# Main.net
KiCad netlist of a schematic drawn in Altium Designer
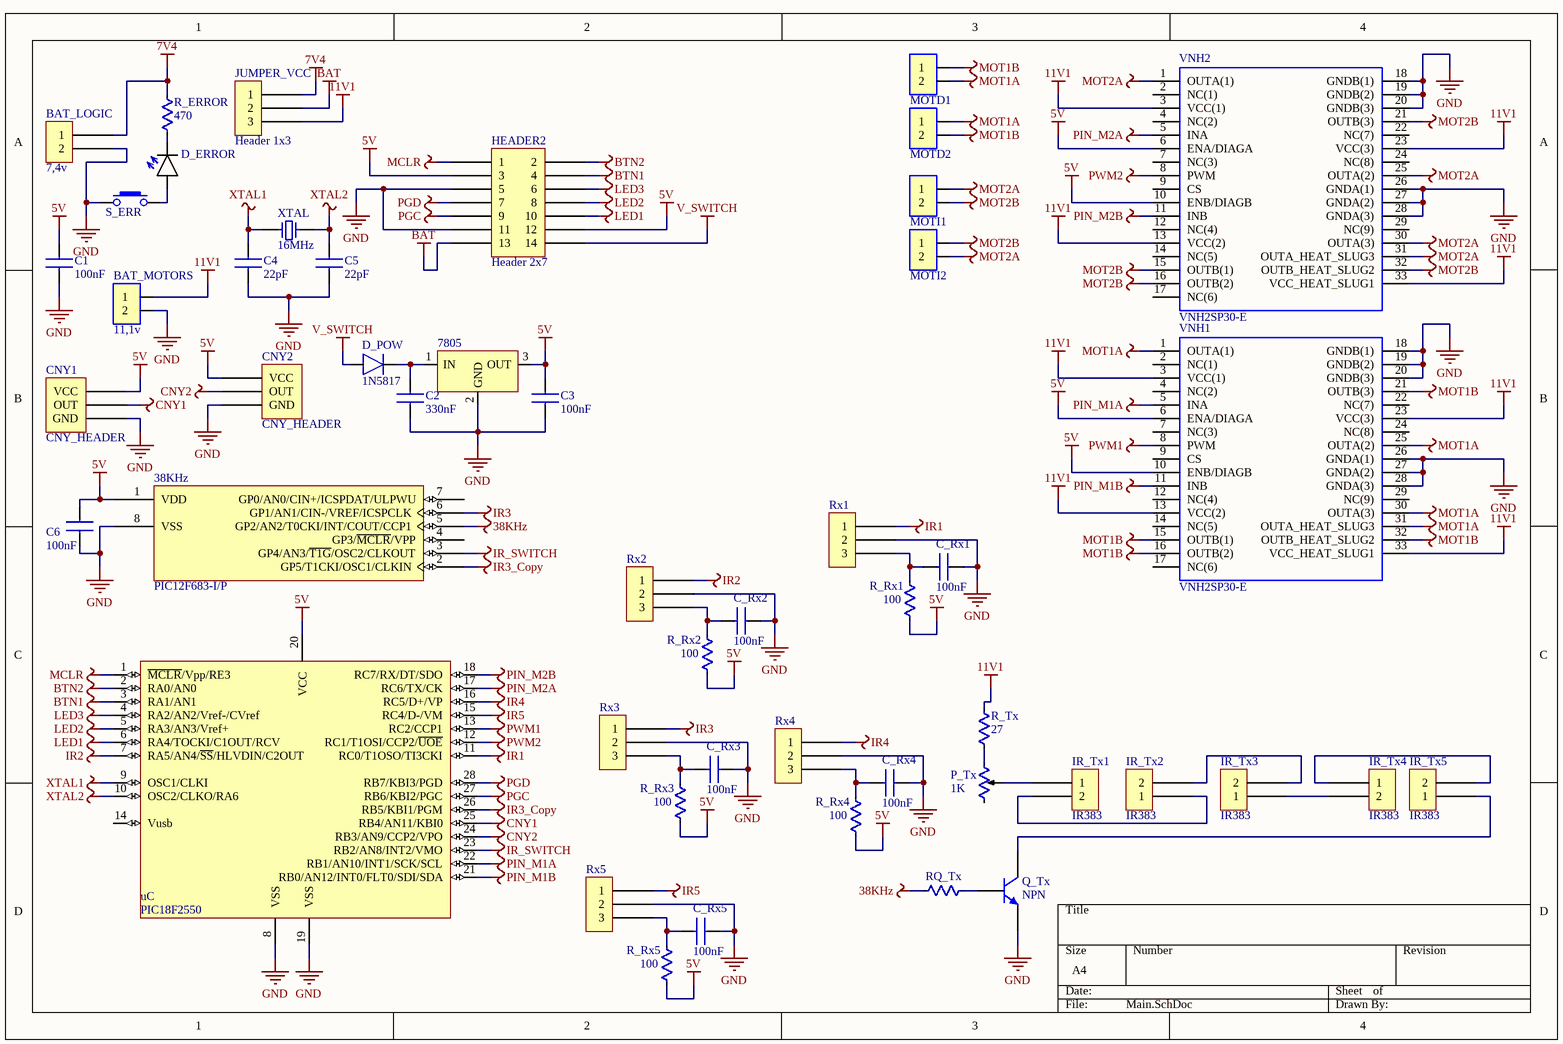
[diagram p0: Main.SchDoc]

(export (version "E")
  (design (tool "Eeschema 10.0.6"))
  (components
    (comp (ref "38KHz")
      (value "PIC12F683-I/P")
      (footprint "PDIP300-P8")
      (fields (field (name "PUBLISHER") "Altium Limited"))
      (libsource (lib "Microchip Microcontroller 8-Bit PIC12") (part "PIC12F683-I/P"))
    )
    (comp (ref "7805")
      (value "LM78XX")
      (footprint "TO-220-STRAIGHT")
      (libsource (lib "AltiumLibrary") (part "LM78XX"))
    )
    (comp (ref "BAT_LOGIC")
      (value "7,4v")
      (footprint "HEADER 1x2")
      (libsource (lib "") (part "Header 1x2_1"))
    )
    (comp (ref "BAT_MOTORS")
      (value "11,1v")
      (footprint "BLOCK_TERMINAL-2")
      (libsource (lib "AltiumLibrary") (part "2-BLOCK_TERMINAL"))
    )
    (comp (ref "C1")
      (value "100nF")
      (footprint "CAP-CER")
      (fields (field (name "Comment") "CAP-CER"))
      (libsource (lib "AltiumLibrary") (part "CAP-CER"))
    )
    (comp (ref "C2")
      (value "330nF")
      (footprint "CAP-CER")
      (fields (field (name "Comment") "CAP-CER"))
      (libsource (lib "AltiumLibrary") (part "CAP-CER"))
    )
    (comp (ref "C3")
      (value "100nF")
      (footprint "CAP-CER")
      (fields (field (name "Comment") "CAP-CER"))
      (libsource (lib "AltiumLibrary") (part "CAP-CER"))
    )
    (comp (ref "C4")
      (value "22pF")
      (footprint "CAP-CER")
      (fields (field (name "Comment") "CAP-CER"))
      (libsource (lib "AltiumLibrary") (part "CAP-CER"))
    )
    (comp (ref "C5")
      (value "22pF")
      (footprint "CAP-CER")
      (fields (field (name "Comment") "CAP-CER"))
      (libsource (lib "AltiumLibrary") (part "CAP-CER"))
    )
    (comp (ref "C6")
      (value "100nF")
      (footprint "CAP-CER")
      (fields (field (name "Comment") "CAP-CER"))
      (libsource (lib "AltiumLibrary") (part "CAP-CER"))
    )
    (comp (ref "CNY1")
      (value "CNY_HEADER")
      (footprint "CNY_HEADER")
      (libsource (lib "") (part "CNY_HEADER_1"))
    )
    (comp (ref "CNY2")
      (value "CNY_HEADER")
      (footprint "CNY_HEADER")
      (libsource (lib "AltiumLibrary") (part "CNY_HEADER"))
    )
    (comp (ref "C_Rx1")
      (value "100nF")
      (footprint "CAP-CER")
      (fields (field (name "Comment") "CAP-CER"))
      (libsource (lib "AltiumLibrary") (part "CAP-CER"))
    )
    (comp (ref "C_Rx2")
      (value "100nF")
      (footprint "CAP-CER")
      (fields (field (name "Comment") "CAP-CER"))
      (libsource (lib "AltiumLibrary") (part "CAP-CER"))
    )
    (comp (ref "C_Rx3")
      (value "100nF")
      (footprint "CAP-CER")
      (fields (field (name "Comment") "CAP-CER"))
      (libsource (lib "AltiumLibrary") (part "CAP-CER"))
    )
    (comp (ref "C_Rx4")
      (value "100nF")
      (footprint "CAP-CER")
      (fields (field (name "Comment") "CAP-CER"))
      (libsource (lib "AltiumLibrary") (part "CAP-CER"))
    )
    (comp (ref "C_Rx5")
      (value "100nF")
      (footprint "CAP-CER")
      (fields (field (name "Comment") "CAP-CER"))
      (libsource (lib "AltiumLibrary") (part "CAP-CER"))
    )
    (comp (ref "D_ERROR")
      (value "LED")
      (footprint "LED-3MM-RED")
      (libsource (lib "AltiumLibrary") (part "LED"))
    )
    (comp (ref "D_POW")
      (value "DIODE")
      (footprint "DO-41")
      (fields (field (name "NAME") "1N5817"))
      (libsource (lib "AltiumLibrary") (part "DIODE"))
    )
    (comp (ref "HEADER2")
      (value "Header 2x7")
      (footprint "HEADER 2x7")
      (libsource (lib "AltiumLibrary") (part "Header 2x7"))
    )
    (comp (ref "IR_Tx1")
      (value "IR383")
      (footprint "HEADER 1x2")
      (libsource (lib "AltiumLibrary") (part "Header 1x2"))
    )
    (comp (ref "IR_Tx2") (value "IR383") (footprint "HEADER 1x2") (libsource (lib "") (part "Header 1x2_2")))
    (comp (ref "IR_Tx3") (value "IR383") (footprint "HEADER 1x2") (libsource (lib "") (part "Header 1x2_2")))
    (comp (ref "IR_Tx4")
      (value "IR383")
      (footprint "HEADER 1x2")
      (libsource (lib "AltiumLibrary") (part "Header 1x2"))
    )
    (comp (ref "IR_Tx5") (value "IR383") (footprint "HEADER 1x2") (libsource (lib "") (part "Header 1x2_2")))
    (comp (ref "JUMPER_VCC")
      (value "Header 1x3")
      (footprint "Header 1x3")
      (libsource (lib "AltiumLibrary") (part "Header 1x3"))
    )
    (comp (ref "MOTD1")
      (value "2-BLOCK_TERMINAL")
      (footprint "BLOCK_TERMINAL-2")
      (libsource (lib "AltiumLibrary") (part "2-BLOCK_TERMINAL"))
    )
    (comp (ref "MOTD2")
      (value "2-BLOCK_TERMINAL")
      (footprint "BLOCK_TERMINAL-2")
      (libsource (lib "AltiumLibrary") (part "2-BLOCK_TERMINAL"))
    )
    (comp (ref "MOTI1")
      (value "2-BLOCK_TERMINAL")
      (footprint "BLOCK_TERMINAL-2")
      (libsource (lib "AltiumLibrary") (part "2-BLOCK_TERMINAL"))
    )
    (comp (ref "MOTI2")
      (value "2-BLOCK_TERMINAL")
      (footprint "BLOCK_TERMINAL-2")
      (libsource (lib "AltiumLibrary") (part "2-BLOCK_TERMINAL"))
    )
    (comp (ref "P_Tx")
      (value "1K")
      (footprint "POT-10TURN")
      (fields (field (name "Comment") "POT"))
      (libsource (lib "AltiumLibrary") (part "POT"))
    )
    (comp (ref "Q_Tx") (value "NPN") (footprint "TO-92") (libsource (lib "AltiumLibrary") (part "NPN")))
    (comp (ref "RQ_Tx") (value "RES") (footprint "RES-Axial-400mil") (libsource (lib "") (part "RES_1")))
    (comp (ref "Rx1")
      (value "Header 1x3")
      (footprint "Header 1x3")
      (libsource (lib "AltiumLibrary") (part "Header 1x3"))
    )
    (comp (ref "Rx2")
      (value "Header 1x3")
      (footprint "Header 1x3")
      (libsource (lib "AltiumLibrary") (part "Header 1x3"))
    )
    (comp (ref "Rx3")
      (value "Header 1x3")
      (footprint "Header 1x3")
      (libsource (lib "AltiumLibrary") (part "Header 1x3"))
    )
    (comp (ref "Rx4")
      (value "Header 1x3")
      (footprint "Header 1x3")
      (libsource (lib "AltiumLibrary") (part "Header 1x3"))
    )
    (comp (ref "Rx5")
      (value "Header 1x3")
      (footprint "Header 1x3")
      (libsource (lib "AltiumLibrary") (part "Header 1x3"))
    )
    (comp (ref "R_ERROR")
      (value "470")
      (footprint "RES-Axial-400mil")
      (fields (field (name "Comment") "RES"))
      (libsource (lib "AltiumLibrary") (part "RES"))
    )
    (comp (ref "R_Rx1")
      (value "100")
      (footprint "RES-Axial-400mil")
      (fields (field (name "Comment") "RES"))
      (libsource (lib "AltiumLibrary") (part "RES"))
    )
    (comp (ref "R_Rx2")
      (value "100")
      (footprint "RES-Axial-400mil")
      (fields (field (name "Comment") "RES"))
      (libsource (lib "AltiumLibrary") (part "RES"))
    )
    (comp (ref "R_Rx3")
      (value "100")
      (footprint "RES-Axial-400mil")
      (fields (field (name "Comment") "RES"))
      (libsource (lib "AltiumLibrary") (part "RES"))
    )
    (comp (ref "R_Rx4")
      (value "100")
      (footprint "RES-Axial-400mil")
      (fields (field (name "Comment") "RES"))
      (libsource (lib "AltiumLibrary") (part "RES"))
    )
    (comp (ref "R_Rx5")
      (value "100")
      (footprint "RES-Axial-400mil")
      (fields (field (name "Comment") "RES"))
      (libsource (lib "AltiumLibrary") (part "RES"))
    )
    (comp (ref "R_Tx")
      (value "27")
      (footprint "RES-Axial-400mil")
      (fields (field (name "Comment") "RES"))
      (libsource (lib "AltiumLibrary") (part "RES"))
    )
    (comp (ref "S_ERR")
      (value "BUTTON_SMALL_4PIN")
      (footprint "TACT_SWITCH-SMALL-4PIN")
      (libsource (lib "AltiumLibrary") (part "BUTTON_SMALL_4PIN"))
    )
    (comp (ref "uC")
      (value "PIC18F2550")
      (footprint "DIP28")
      (libsource (lib "AltiumLibrary") (part "PIC18F2550"))
    )
    (comp (ref "VNH1")
      (value "VNH2SP30-E")
      (footprint "MULTIPOWER-SO-30")
      (fields (field (name "DIGIKEY PART NUMBER") "497-4500-5-ND"))
      (libsource (lib "AltiumLibrary") (part "VNH2SP30-E"))
    )
    (comp (ref "VNH2")
      (value "VNH2SP30-E")
      (footprint "MULTIPOWER-SO-30")
      (fields (field (name "DIGIKEY PART NUMBER") "497-4500-5-ND"))
      (libsource (lib "AltiumLibrary") (part "VNH2SP30-E"))
    )
    (comp (ref "XTAL")
      (value "XTAL")
      (footprint "HC-49/S")
      (fields (field (name "FREQUENCY") "16MHz"))
      (libsource (lib "AltiumLibrary") (part "XTAL"))
    )
  )
  (nets
    (net (code "1") (name "5V") (class "Default")
      (node (ref "38KHz") (pin "1") (pinfunction "VDD_1") (pintype "power_in"))
      (node (ref "7805") (pin "3") (pinfunction "OUT_3") (pintype "power_in"))
      (node (ref "C1") (pin "2") (pintype "passive"))
      (node (ref "C3") (pin "2") (pintype "passive"))
      (node (ref "C6") (pin "2") (pintype "passive"))
      (node (ref "CNY1") (pin "2") (pinfunction "VCC_2") (pintype "passive"))
      (node (ref "CNY2") (pin "2") (pinfunction "VCC_2") (pintype "passive"))
      (node (ref "HEADER2") (pin "12") (pinfunction "12_12") (pintype "passive"))
      (node (ref "HEADER2") (pin "3") (pinfunction "3_3") (pintype "passive"))
      (node (ref "R_Rx1") (pin "1") (pintype "passive"))
      (node (ref "R_Rx2") (pin "1") (pintype "passive"))
      (node (ref "R_Rx3") (pin "1") (pintype "passive"))
      (node (ref "R_Rx4") (pin "1") (pintype "passive"))
      (node (ref "R_Rx5") (pin "1") (pintype "passive"))
      (node (ref "VNH1") (pin "10") (pinfunction "ENB/DIAGB_10") (pintype "passive"))
      (node (ref "VNH1") (pin "6") (pinfunction "ENA/DIAGA_6") (pintype "passive"))
      (node (ref "VNH2") (pin "10") (pinfunction "ENB/DIAGB_10") (pintype "passive"))
      (node (ref "VNH2") (pin "6") (pinfunction "ENA/DIAGA_6") (pintype "passive"))
      (node (ref "uC") (pin "20") (pinfunction "VCC_20") (pintype "power_in"))
    )
    (net (code "2") (name "7V4") (class "Default")
      (node (ref "BAT_LOGIC") (pin "1") (pinfunction "1_1") (pintype "passive"))
      (node (ref "JUMPER_VCC") (pin "1") (pinfunction "1_1") (pintype "passive"))
      (node (ref "R_ERROR") (pin "2") (pintype "passive"))
    )
    (net (code "3") (name "11V1") (class "Default")
      (node (ref "BAT_MOTORS") (pin "1") (pinfunction "1_1") (pintype "passive"))
      (node (ref "JUMPER_VCC") (pin "3") (pinfunction "3_3") (pintype "passive"))
      (node (ref "R_Tx") (pin "2") (pintype "passive"))
      (node (ref "VNH1") (pin "13") (pinfunction "VCC(2)_13") (pintype "passive"))
      (node (ref "VNH1") (pin "23") (pinfunction "VCC(3)_23") (pintype "passive"))
      (node (ref "VNH1") (pin "3") (pinfunction "VCC(1)_3") (pintype "passive"))
      (node (ref "VNH1") (pin "33") (pinfunction "VCC_HEAT_SLUG1_33") (pintype "passive"))
      (node (ref "VNH2") (pin "13") (pinfunction "VCC(2)_13") (pintype "passive"))
      (node (ref "VNH2") (pin "23") (pinfunction "VCC(3)_23") (pintype "passive"))
      (node (ref "VNH2") (pin "3") (pinfunction "VCC(1)_3") (pintype "passive"))
      (node (ref "VNH2") (pin "33") (pinfunction "VCC_HEAT_SLUG1_33") (pintype "passive"))
    )
    (net (code "4") (name "38KHz") (class "Default")
      (node (ref "38KHz") (pin "5") (pinfunction "GP2/AN2/T0CKI/INT/COUT/CCP1_5") (pintype "bidirectional"))
      (node (ref "RQ_Tx") (pin "1") (pintype "passive"))
    )
    (net (code "5") (name "BAT") (class "Default")
      (node (ref "HEADER2") (pin "13") (pinfunction "13_13") (pintype "passive"))
      (node (ref "JUMPER_VCC") (pin "2") (pinfunction "2_2") (pintype "passive"))
    )
    (net (code "6") (name "BTN1") (class "Default")
      (node (ref "HEADER2") (pin "4") (pinfunction "4_4") (pintype "passive"))
      (node (ref "uC") (pin "3") (pinfunction "RA1/AN1_3") (pintype "bidirectional"))
    )
    (net (code "7") (name "BTN2") (class "Default")
      (node (ref "HEADER2") (pin "2") (pinfunction "2_2") (pintype "passive"))
      (node (ref "uC") (pin "2") (pinfunction "RA0/AN0_2") (pintype "bidirectional"))
    )
    (net (code "8") (name "CNY1") (class "Default")
      (node (ref "CNY1") (pin "3") (pinfunction "OUT_3") (pintype "passive"))
      (node (ref "uC") (pin "25") (pinfunction "RB4/AN11/KBI0_25") (pintype "bidirectional"))
    )
    (net (code "9") (name "CNY2") (class "Default")
      (node (ref "CNY2") (pin "3") (pinfunction "OUT_3") (pintype "passive"))
      (node (ref "uC") (pin "24") (pinfunction "RB3/AN9/CCP2/VPO_24") (pintype "bidirectional"))
    )
    (net (code "10") (name "GND") (class "Default")
      (node (ref "38KHz") (pin "8") (pinfunction "VSS_8") (pintype "power_in"))
      (node (ref "7805") (pin "2") (pinfunction "GND_2") (pintype "power_in"))
      (node (ref "BAT_LOGIC") (pin "2") (pinfunction "2_2") (pintype "passive"))
      (node (ref "BAT_MOTORS") (pin "2") (pinfunction "2_2") (pintype "passive"))
      (node (ref "C1") (pin "1") (pintype "passive"))
      (node (ref "C2") (pin "1") (pintype "passive"))
      (node (ref "C3") (pin "1") (pintype "passive"))
      (node (ref "C4") (pin "1") (pintype "passive"))
      (node (ref "C5") (pin "1") (pintype "passive"))
      (node (ref "C6") (pin "1") (pintype "passive"))
      (node (ref "CNY1") (pin "1") (pinfunction "GND_1") (pintype "passive"))
      (node (ref "CNY2") (pin "1") (pinfunction "GND_1") (pintype "passive"))
      (node (ref "C_Rx1") (pin "2") (pintype "passive"))
      (node (ref "C_Rx2") (pin "2") (pintype "passive"))
      (node (ref "C_Rx3") (pin "2") (pintype "passive"))
      (node (ref "C_Rx4") (pin "2") (pintype "passive"))
      (node (ref "C_Rx5") (pin "2") (pintype "passive"))
      (node (ref "HEADER2") (pin "11") (pinfunction "11_11") (pintype "passive"))
      (node (ref "HEADER2") (pin "5") (pinfunction "5_5") (pintype "passive"))
      (node (ref "Q_Tx") (pin "E") (pinfunction "E_E") (pintype "passive"))
      (node (ref "Rx1") (pin "2") (pinfunction "2_2") (pintype "passive"))
      (node (ref "Rx2") (pin "2") (pinfunction "2_2") (pintype "passive"))
      (node (ref "Rx3") (pin "2") (pinfunction "2_2") (pintype "passive"))
      (node (ref "Rx4") (pin "2") (pinfunction "2_2") (pintype "passive"))
      (node (ref "Rx5") (pin "2") (pinfunction "2_2") (pintype "passive"))
      (node (ref "S_ERR") (pin "1") (pintype "passive"))
      (node (ref "VNH1") (pin "18") (pinfunction "GNDB(1)_18") (pintype "passive"))
      (node (ref "VNH1") (pin "19") (pinfunction "GNDB(2)_19") (pintype "passive"))
      (node (ref "VNH1") (pin "20") (pinfunction "GNDB(3)_20") (pintype "passive"))
      (node (ref "VNH1") (pin "26") (pinfunction "GNDA(1)_26") (pintype "passive"))
      (node (ref "VNH1") (pin "27") (pinfunction "GNDA(2)_27") (pintype "passive"))
      (node (ref "VNH1") (pin "28") (pinfunction "GNDA(3)_28") (pintype "passive"))
      (node (ref "VNH2") (pin "18") (pinfunction "GNDB(1)_18") (pintype "passive"))
      (node (ref "VNH2") (pin "19") (pinfunction "GNDB(2)_19") (pintype "passive"))
      (node (ref "VNH2") (pin "20") (pinfunction "GNDB(3)_20") (pintype "passive"))
      (node (ref "VNH2") (pin "26") (pinfunction "GNDA(1)_26") (pintype "passive"))
      (node (ref "VNH2") (pin "27") (pinfunction "GNDA(2)_27") (pintype "passive"))
      (node (ref "VNH2") (pin "28") (pinfunction "GNDA(3)_28") (pintype "passive"))
      (node (ref "uC") (pin "19") (pinfunction "VSS_19") (pintype "power_in"))
      (node (ref "uC") (pin "8") (pinfunction "VSS_8") (pintype "power_in"))
    )
    (net (code "11") (name "IR1") (class "Default")
      (node (ref "Rx1") (pin "1") (pinfunction "1_1") (pintype "passive"))
      (node (ref "uC") (pin "11") (pinfunction "RC0/T1OSO/TI3CKI_11") (pintype "bidirectional"))
    )
    (net (code "12") (name "IR2") (class "Default")
      (node (ref "Rx2") (pin "1") (pinfunction "1_1") (pintype "passive"))
      (node (ref "uC") (pin "7") (pinfunction "RA5/AN4/~{SS}/HLVDIN/C2OUT_7") (pintype "bidirectional"))
    )
    (net (code "13") (name "IR3") (class "Default")
      (node (ref "38KHz") (pin "6") (pinfunction "GP1/AN1/CIN-/VREF/ICSPCLK_6") (pintype "bidirectional"))
      (node (ref "Rx3") (pin "1") (pinfunction "1_1") (pintype "passive"))
    )
    (net (code "14") (name "IR3_Copy") (class "Default")
      (node (ref "38KHz") (pin "2") (pinfunction "GP5/T1CKI/OSC1/CLKIN_2") (pintype "bidirectional"))
      (node (ref "uC") (pin "26") (pinfunction "RB5/KBI1/PGM_26") (pintype "bidirectional"))
    )
    (net (code "15") (name "IR4") (class "Default")
      (node (ref "Rx4") (pin "1") (pinfunction "1_1") (pintype "passive"))
      (node (ref "uC") (pin "16") (pinfunction "RC5/D+/VP_16") (pintype "bidirectional"))
    )
    (net (code "16") (name "IR5") (class "Default")
      (node (ref "Rx5") (pin "1") (pinfunction "1_1") (pintype "passive"))
      (node (ref "uC") (pin "15") (pinfunction "RC4/D-/VM_15") (pintype "bidirectional"))
    )
    (net (code "17") (name "IR_SWITCH") (class "Default")
      (node (ref "38KHz") (pin "3") (pinfunction "GP4/AN3/~{T1G}/OSC2/CLKOUT_3") (pintype "bidirectional"))
      (node (ref "uC") (pin "23") (pinfunction "RB2/AN8/INT2/VMO_23") (pintype "bidirectional"))
    )
    (net (code "18") (name "LED1") (class "Default")
      (node (ref "HEADER2") (pin "10") (pinfunction "10_10") (pintype "passive"))
      (node (ref "uC") (pin "6") (pinfunction "RA4/TOCKI/C1OUT/RCV_6") (pintype "bidirectional"))
    )
    (net (code "19") (name "LED2") (class "Default")
      (node (ref "HEADER2") (pin "8") (pinfunction "8_8") (pintype "passive"))
      (node (ref "uC") (pin "5") (pinfunction "RA3/AN3/Vref+_5") (pintype "bidirectional"))
    )
    (net (code "20") (name "LED3") (class "Default")
      (node (ref "HEADER2") (pin "6") (pinfunction "6_6") (pintype "passive"))
      (node (ref "uC") (pin "4") (pinfunction "RA2/AN2/Vref-/CVref_4") (pintype "bidirectional"))
    )
    (net (code "21") (name "MCLR") (class "Default")
      (node (ref "HEADER2") (pin "1") (pinfunction "1_1") (pintype "passive"))
      (node (ref "uC") (pin "1") (pinfunction "~{MCLR}/Vpp/RE3_1") (pintype "bidirectional"))
    )
    (net (code "22") (name "MOT1A") (class "Default")
      (node (ref "MOTD1") (pin "2") (pinfunction "2_2") (pintype "passive"))
      (node (ref "MOTD2") (pin "1") (pinfunction "1_1") (pintype "passive"))
      (node (ref "VNH1") (pin "1") (pinfunction "OUTA(1)_1") (pintype "passive"))
      (node (ref "VNH1") (pin "25") (pinfunction "OUTA(2)_25") (pintype "passive"))
      (node (ref "VNH1") (pin "30") (pinfunction "OUTA(3)_30") (pintype "passive"))
      (node (ref "VNH1") (pin "31") (pinfunction "OUTA_HEAT_SLUG3_31") (pintype "passive"))
    )
    (net (code "23") (name "MOT1B") (class "Default")
      (node (ref "MOTD1") (pin "1") (pinfunction "1_1") (pintype "passive"))
      (node (ref "MOTD2") (pin "2") (pinfunction "2_2") (pintype "passive"))
      (node (ref "VNH1") (pin "15") (pinfunction "OUTB(1)_15") (pintype "passive"))
      (node (ref "VNH1") (pin "16") (pinfunction "OUTB(2)_16") (pintype "passive"))
      (node (ref "VNH1") (pin "21") (pinfunction "OUTB(3)_21") (pintype "passive"))
      (node (ref "VNH1") (pin "32") (pinfunction "OUTB_HEAT_SLUG2_32") (pintype "passive"))
    )
    (net (code "24") (name "MOT2A") (class "Default")
      (node (ref "MOTI1") (pin "1") (pinfunction "1_1") (pintype "passive"))
      (node (ref "MOTI2") (pin "2") (pinfunction "2_2") (pintype "passive"))
      (node (ref "VNH2") (pin "1") (pinfunction "OUTA(1)_1") (pintype "passive"))
      (node (ref "VNH2") (pin "25") (pinfunction "OUTA(2)_25") (pintype "passive"))
      (node (ref "VNH2") (pin "30") (pinfunction "OUTA(3)_30") (pintype "passive"))
      (node (ref "VNH2") (pin "31") (pinfunction "OUTA_HEAT_SLUG3_31") (pintype "passive"))
    )
    (net (code "25") (name "MOT2B") (class "Default")
      (node (ref "MOTI1") (pin "2") (pinfunction "2_2") (pintype "passive"))
      (node (ref "MOTI2") (pin "1") (pinfunction "1_1") (pintype "passive"))
      (node (ref "VNH2") (pin "15") (pinfunction "OUTB(1)_15") (pintype "passive"))
      (node (ref "VNH2") (pin "16") (pinfunction "OUTB(2)_16") (pintype "passive"))
      (node (ref "VNH2") (pin "21") (pinfunction "OUTB(3)_21") (pintype "passive"))
      (node (ref "VNH2") (pin "32") (pinfunction "OUTB_HEAT_SLUG2_32") (pintype "passive"))
    )
    (net (code "26") (name "Net-(7805-IN)") (class "Default")
      (node (ref "7805") (pin "1") (pinfunction "IN_1") (pintype "power_in"))
      (node (ref "C2") (pin "2") (pintype "passive"))
      (node (ref "D_POW") (pin "K") (pintype "passive"))
    )
    (net (code "27") (name "Net-(C_Rx1-Pad1)") (class "Default")
      (node (ref "C_Rx1") (pin "1") (pintype "passive"))
      (node (ref "R_Rx1") (pin "2") (pintype "passive"))
      (node (ref "Rx1") (pin "3") (pinfunction "3_3") (pintype "passive"))
    )
    (net (code "28") (name "Net-(C_Rx2-Pad1)") (class "Default")
      (node (ref "C_Rx2") (pin "1") (pintype "passive"))
      (node (ref "R_Rx2") (pin "2") (pintype "passive"))
      (node (ref "Rx2") (pin "3") (pinfunction "3_3") (pintype "passive"))
    )
    (net (code "29") (name "Net-(C_Rx3-Pad1)") (class "Default")
      (node (ref "C_Rx3") (pin "1") (pintype "passive"))
      (node (ref "R_Rx3") (pin "2") (pintype "passive"))
      (node (ref "Rx3") (pin "3") (pinfunction "3_3") (pintype "passive"))
    )
    (net (code "30") (name "Net-(C_Rx4-Pad1)") (class "Default")
      (node (ref "C_Rx4") (pin "1") (pintype "passive"))
      (node (ref "R_Rx4") (pin "2") (pintype "passive"))
      (node (ref "Rx4") (pin "3") (pinfunction "3_3") (pintype "passive"))
    )
    (net (code "31") (name "Net-(C_Rx5-Pad1)") (class "Default")
      (node (ref "C_Rx5") (pin "1") (pintype "passive"))
      (node (ref "R_Rx5") (pin "2") (pintype "passive"))
      (node (ref "Rx5") (pin "3") (pinfunction "3_3") (pintype "passive"))
    )
    (net (code "32") (name "Net-(D_ERROR-PadA)") (class "Default")
      (node (ref "D_ERROR") (pin "A") (pintype "passive"))
      (node (ref "S_ERR") (pin "2") (pintype "passive"))
    )
    (net (code "33") (name "Net-(D_ERROR-PadK)") (class "Default")
      (node (ref "D_ERROR") (pin "K") (pintype "passive"))
      (node (ref "R_ERROR") (pin "1") (pintype "passive"))
    )
    (net (code "34") (name "Net-(IR_Tx1-Pad1)") (class "Default")
      (node (ref "IR_Tx1") (pin "1") (pinfunction "1_1") (pintype "passive"))
      (node (ref "P_Tx") (pin "2") (pintype "passive"))
    )
    (net (code "35") (name "Net-(IR_Tx1-Pad2)") (class "Default")
      (node (ref "IR_Tx1") (pin "2") (pinfunction "2_2") (pintype "passive"))
      (node (ref "IR_Tx2") (pin "1") (pinfunction "1_1") (pintype "passive"))
    )
    (net (code "36") (name "Net-(IR_Tx2-Pad2)") (class "Default")
      (node (ref "IR_Tx2") (pin "2") (pinfunction "2_2") (pintype "passive"))
      (node (ref "IR_Tx3") (pin "2") (pinfunction "2_2") (pintype "passive"))
    )
    (net (code "37") (name "Net-(IR_Tx3-Pad1)") (class "Default")
      (node (ref "IR_Tx3") (pin "1") (pinfunction "1_1") (pintype "passive"))
      (node (ref "IR_Tx4") (pin "2") (pinfunction "2_2") (pintype "passive"))
    )
    (net (code "38") (name "Net-(IR_Tx4-Pad1)") (class "Default")
      (node (ref "IR_Tx4") (pin "1") (pinfunction "1_1") (pintype "passive"))
      (node (ref "IR_Tx5") (pin "2") (pinfunction "2_2") (pintype "passive"))
    )
    (net (code "39") (name "Net-(IR_Tx5-Pad1)") (class "Default")
      (node (ref "IR_Tx5") (pin "1") (pinfunction "1_1") (pintype "passive"))
      (node (ref "Q_Tx") (pin "C") (pinfunction "C_C") (pintype "passive"))
    )
    (net (code "40") (name "Net-(P_Tx-Pad1)") (class "Default")
      (node (ref "P_Tx") (pin "1") (pintype "passive"))
      (node (ref "R_Tx") (pin "1") (pintype "passive"))
    )
    (net (code "41") (name "Net-(Q_Tx-PadB)") (class "Default")
      (node (ref "Q_Tx") (pin "B") (pinfunction "B_B") (pintype "passive"))
      (node (ref "RQ_Tx") (pin "2") (pintype "passive"))
    )
    (net (code "42") (name "PGC") (class "Default")
      (node (ref "HEADER2") (pin "9") (pinfunction "9_9") (pintype "passive"))
      (node (ref "uC") (pin "27") (pinfunction "RB6/KBI2/PGC_27") (pintype "bidirectional"))
    )
    (net (code "43") (name "PGD") (class "Default")
      (node (ref "HEADER2") (pin "7") (pinfunction "7_7") (pintype "passive"))
      (node (ref "uC") (pin "28") (pinfunction "RB7/KBI3/PGD_28") (pintype "bidirectional"))
    )
    (net (code "44") (name "PIN_M1A") (class "Default")
      (node (ref "VNH1") (pin "5") (pinfunction "INA_5") (pintype "passive"))
      (node (ref "uC") (pin "22") (pinfunction "RB1/AN10/INT1/SCK/SCL_22") (pintype "bidirectional"))
    )
    (net (code "45") (name "PIN_M1B") (class "Default")
      (node (ref "VNH1") (pin "11") (pinfunction "INB_11") (pintype "passive"))
      (node (ref "uC") (pin "21") (pinfunction "RB0/AN12/INT0/FLT0/SDI/SDA_21") (pintype "bidirectional"))
    )
    (net (code "46") (name "PIN_M2A") (class "Default")
      (node (ref "VNH2") (pin "5") (pinfunction "INA_5") (pintype "passive"))
      (node (ref "uC") (pin "17") (pinfunction "RC6/TX/CK_17") (pintype "bidirectional"))
    )
    (net (code "47") (name "PIN_M2B") (class "Default")
      (node (ref "VNH2") (pin "11") (pinfunction "INB_11") (pintype "passive"))
      (node (ref "uC") (pin "18") (pinfunction "RC7/RX/DT/SDO_18") (pintype "bidirectional"))
    )
    (net (code "48") (name "PWM1") (class "Default")
      (node (ref "VNH1") (pin "8") (pinfunction "PWM_8") (pintype "passive"))
      (node (ref "uC") (pin "13") (pinfunction "RC2/CCP1_13") (pintype "bidirectional"))
    )
    (net (code "49") (name "PWM2") (class "Default")
      (node (ref "VNH2") (pin "8") (pinfunction "PWM_8") (pintype "passive"))
      (node (ref "uC") (pin "12") (pinfunction "RC1/T1OSI/CCP2/~{UOE}_12") (pintype "bidirectional"))
    )
    (net (code "50") (name "V_SWITCH") (class "Default")
      (node (ref "D_POW") (pin "A") (pintype "passive"))
      (node (ref "HEADER2") (pin "14") (pinfunction "14_14") (pintype "passive"))
    )
    (net (code "51") (name "XTAL1") (class "Default")
      (node (ref "C4") (pin "2") (pintype "passive"))
      (node (ref "XTAL") (pin "2") (pintype "passive"))
      (node (ref "uC") (pin "9") (pinfunction "OSC1/CLKI_9") (pintype "bidirectional"))
    )
    (net (code "52") (name "XTAL2") (class "Default")
      (node (ref "C5") (pin "2") (pintype "passive"))
      (node (ref "XTAL") (pin "1") (pintype "passive"))
      (node (ref "uC") (pin "10") (pinfunction "OSC2/CLKO/RA6_10") (pintype "bidirectional"))
    )
    (net (code "53") (name "unconnected-(38KHz-GP0{slash}AN0{slash}CIN+{slash}ICSPDAT{slash}ULPWU-Pad7)") (class "Default")
      (node (ref "38KHz") (pin "7") (pinfunction "GP0/AN0/CIN+/ICSPDAT/ULPWU_7") (pintype "bidirectional"))
    )
    (net (code "54") (name "unconnected-(38KHz-GP3{slash}~{MCLR}{slash}VPP-Pad4)") (class "Default")
      (node (ref "38KHz") (pin "4") (pinfunction "GP3/~{MCLR}/VPP_4") (pintype "bidirectional"))
    )
    (net (code "55") (name "unconnected-(P_Tx-Pad3)") (class "Default")
      (node (ref "P_Tx") (pin "3") (pintype "passive"))
    )
    (net (code "56") (name "unconnected-(VNH1-CS-Pad9)") (class "Default")
      (node (ref "VNH1") (pin "9") (pinfunction "CS_9") (pintype "passive"))
    )
    (net (code "57") (name "unconnected-(VNH1-NC(1)-Pad2)") (class "Default")
      (node (ref "VNH1") (pin "2") (pinfunction "NC(1)_2") (pintype "passive"))
    )
    (net (code "58") (name "unconnected-(VNH1-NC(2)-Pad4)") (class "Default")
      (node (ref "VNH1") (pin "4") (pinfunction "NC(2)_4") (pintype "passive"))
    )
    (net (code "59") (name "unconnected-(VNH1-NC(3)-Pad7)") (class "Default")
      (node (ref "VNH1") (pin "7") (pinfunction "NC(3)_7") (pintype "passive"))
    )
    (net (code "60") (name "unconnected-(VNH1-NC(4)-Pad12)") (class "Default")
      (node (ref "VNH1") (pin "12") (pinfunction "NC(4)_12") (pintype "passive"))
    )
    (net (code "61") (name "unconnected-(VNH1-NC(5)-Pad14)") (class "Default")
      (node (ref "VNH1") (pin "14") (pinfunction "NC(5)_14") (pintype "passive"))
    )
    (net (code "62") (name "unconnected-(VNH1-NC(6)-Pad17)") (class "Default")
      (node (ref "VNH1") (pin "17") (pinfunction "NC(6)_17") (pintype "passive"))
    )
    (net (code "63") (name "unconnected-(VNH1-NC(7)-Pad22)") (class "Default")
      (node (ref "VNH1") (pin "22") (pinfunction "NC(7)_22") (pintype "passive"))
    )
    (net (code "64") (name "unconnected-(VNH1-NC(8)-Pad24)") (class "Default")
      (node (ref "VNH1") (pin "24") (pinfunction "NC(8)_24") (pintype "passive"))
    )
    (net (code "65") (name "unconnected-(VNH1-NC(9)-Pad29)") (class "Default")
      (node (ref "VNH1") (pin "29") (pinfunction "NC(9)_29") (pintype "passive"))
    )
    (net (code "66") (name "unconnected-(VNH2-CS-Pad9)") (class "Default")
      (node (ref "VNH2") (pin "9") (pinfunction "CS_9") (pintype "passive"))
    )
    (net (code "67") (name "unconnected-(VNH2-NC(1)-Pad2)") (class "Default")
      (node (ref "VNH2") (pin "2") (pinfunction "NC(1)_2") (pintype "passive"))
    )
    (net (code "68") (name "unconnected-(VNH2-NC(2)-Pad4)") (class "Default")
      (node (ref "VNH2") (pin "4") (pinfunction "NC(2)_4") (pintype "passive"))
    )
    (net (code "69") (name "unconnected-(VNH2-NC(3)-Pad7)") (class "Default")
      (node (ref "VNH2") (pin "7") (pinfunction "NC(3)_7") (pintype "passive"))
    )
    (net (code "70") (name "unconnected-(VNH2-NC(4)-Pad12)") (class "Default")
      (node (ref "VNH2") (pin "12") (pinfunction "NC(4)_12") (pintype "passive"))
    )
    (net (code "71") (name "unconnected-(VNH2-NC(5)-Pad14)") (class "Default")
      (node (ref "VNH2") (pin "14") (pinfunction "NC(5)_14") (pintype "passive"))
    )
    (net (code "72") (name "unconnected-(VNH2-NC(6)-Pad17)") (class "Default")
      (node (ref "VNH2") (pin "17") (pinfunction "NC(6)_17") (pintype "passive"))
    )
    (net (code "73") (name "unconnected-(VNH2-NC(7)-Pad22)") (class "Default")
      (node (ref "VNH2") (pin "22") (pinfunction "NC(7)_22") (pintype "passive"))
    )
    (net (code "74") (name "unconnected-(VNH2-NC(8)-Pad24)") (class "Default")
      (node (ref "VNH2") (pin "24") (pinfunction "NC(8)_24") (pintype "passive"))
    )
    (net (code "75") (name "unconnected-(VNH2-NC(9)-Pad29)") (class "Default")
      (node (ref "VNH2") (pin "29") (pinfunction "NC(9)_29") (pintype "passive"))
    )
    (net (code "76") (name "unconnected-(uC-Vusb-Pad14)") (class "Default")
      (node (ref "uC") (pin "14") (pinfunction "Vusb_14") (pintype "bidirectional"))
    )
  )
)
